# ASL1101.net
KiCad netlist of a schematic drawn in EAGLE
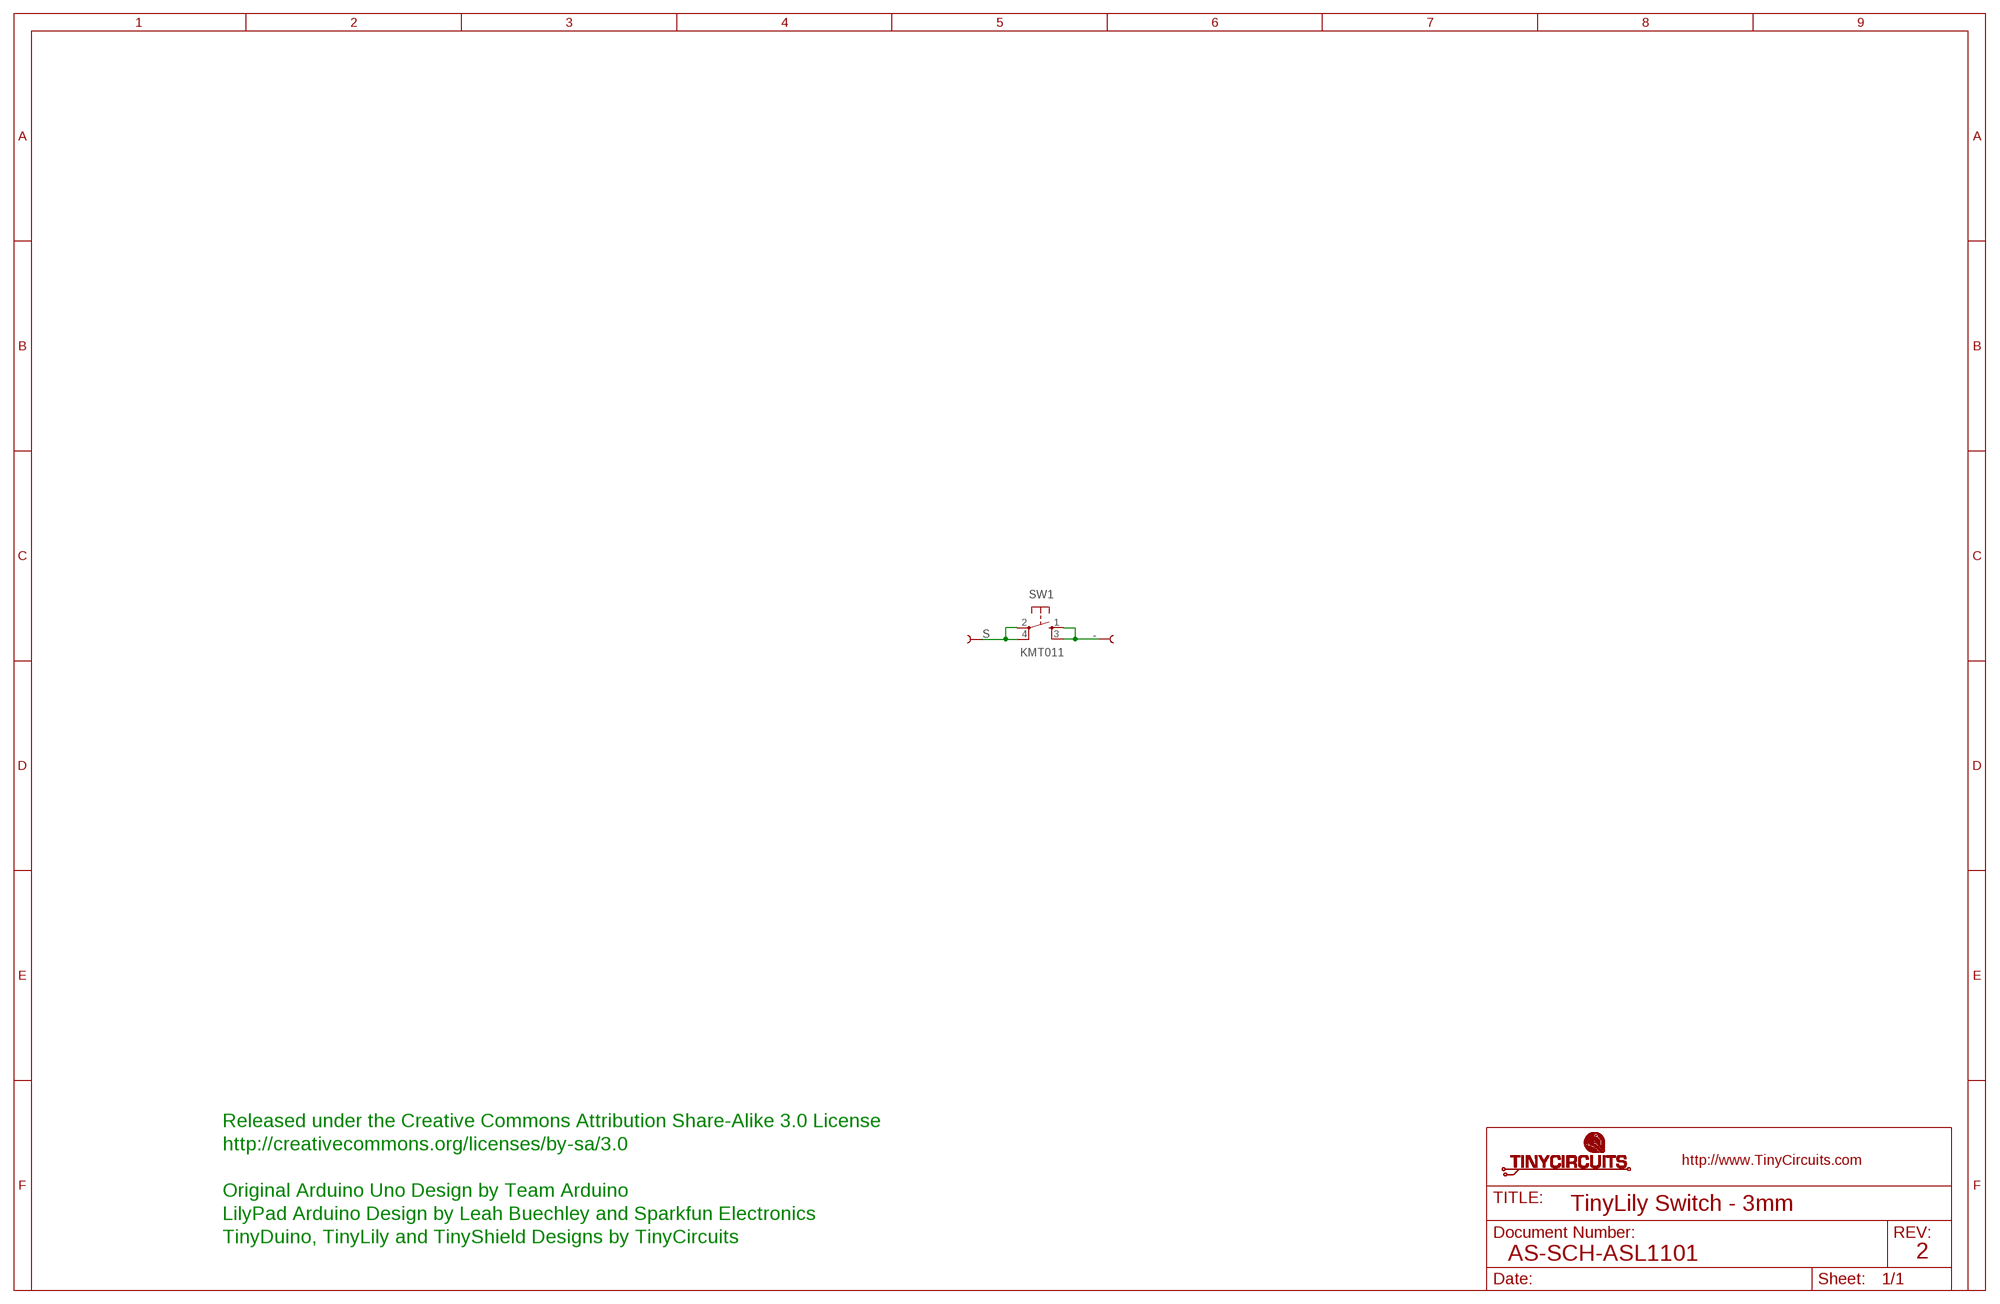
[diagram p0: schematic, sheet 1]

(export (version "E")
  (design (tool "Eeschema 10.0.6"))
  (components
    (comp (ref "SW1")
      (value "KMT011")
      (footprint "eagle-import:KMT011")
      (fields (field (name "PARTNO") "AS-ITM-00041"))
      (libsource (lib "eagle-import") (part "AS-ITM-00041"))
    )
    (comp (ref "U$1")
      (value "SEWTABTH_1206")
      (footprint "eagle-import:SEWTAP_TH_1206")
      (libsource (lib "eagle-import") (part "SEWTABTH_1206"))
    )
    (comp (ref "U$7")
      (value "SEWTABTH_1206")
      (footprint "eagle-import:SEWTAP_TH_1206")
      (libsource (lib "eagle-import") (part "SEWTABTH_1206"))
    )
  )
  (nets
    (net (code "1") (name "/-") (class "Default")
      (node (ref "SW1") (pin "1") (pinfunction "1_1") (pintype "passive"))
      (node (ref "SW1") (pin "3") (pinfunction "3_3") (pintype "passive"))
      (node (ref "U$1") (pin "1") (pinfunction "1_1") (pintype "bidirectional"))
    )
    (net (code "2") (name "/S") (class "Default")
      (node (ref "SW1") (pin "2") (pinfunction "2_2") (pintype "passive"))
      (node (ref "SW1") (pin "4") (pinfunction "4_4") (pintype "passive"))
      (node (ref "U$7") (pin "1") (pinfunction "1_1") (pintype "bidirectional"))
    )
  )
)
